# 6_-_Load_Drivers.net
KiCad netlist of a schematic drawn in Altium Designer
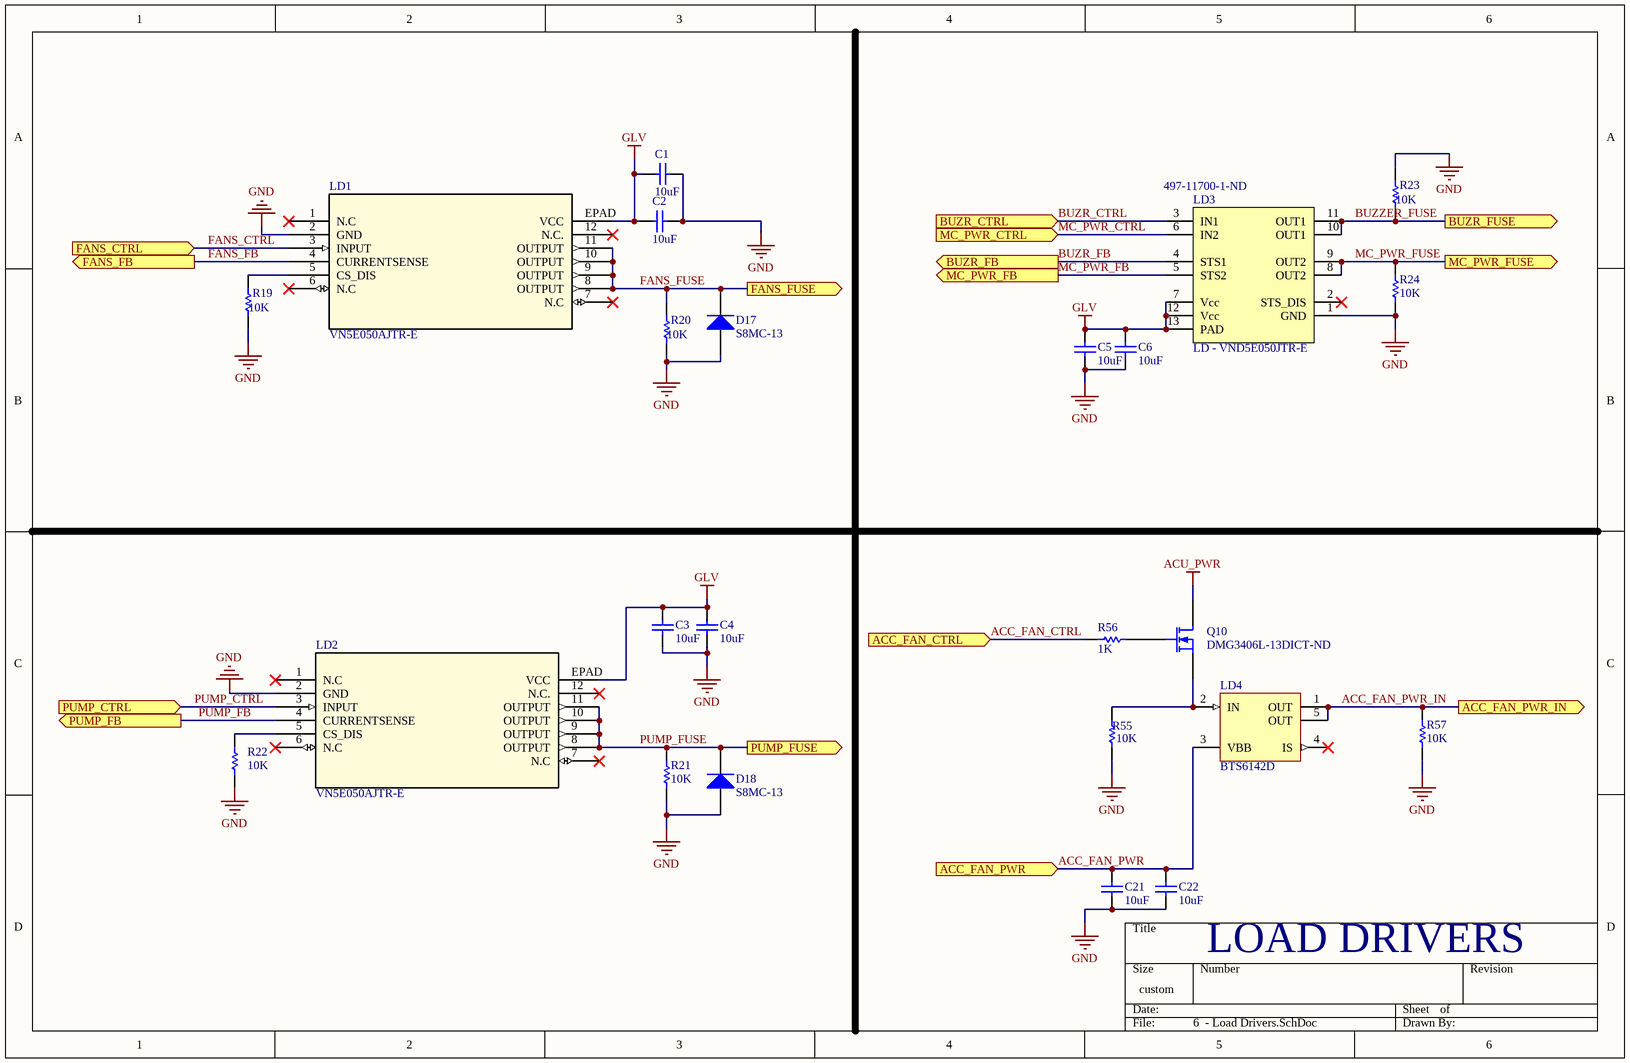
[diagram p0: 6  - Load Drivers.SchDoc]

(export (version "E")
  (design (tool "Eeschema 10.0.6"))
  (components
    (comp (ref "C1")
      (value "10uF")
      (footprint "0603R-generic")
      (description "Capacitor")
      (fields
        (field (name "MANUFACTURER") "Yageo")
        (field (name "MANUFACTURER PART NUMBER") "CC1210ZKY5V8BB106")
      )
      (libsource (lib "Miscellaneous Devices") (part "Cap"))
    )
    (comp (ref "C2")
      (value "10uF")
      (footprint "0603R-generic")
      (description "Capacitor")
      (fields
        (field (name "MANUFACTURER") "Yageo")
        (field (name "MANUFACTURER PART NUMBER") "CC1210ZKY5V8BB106")
      )
      (libsource (lib "Miscellaneous Devices") (part "Cap"))
    )
    (comp (ref "C3")
      (value "10uF")
      (footprint "0603R-generic")
      (description "Capacitor")
      (fields
        (field (name "MANUFACTURER") "Yageo")
        (field (name "MANUFACTURER PART NUMBER") "CC1210ZKY5V8BB106")
      )
      (libsource (lib "Miscellaneous Devices") (part "Cap"))
    )
    (comp (ref "C4")
      (value "10uF")
      (footprint "0603R-generic")
      (description "Capacitor")
      (fields
        (field (name "MANUFACTURER") "Yageo")
        (field (name "MANUFACTURER PART NUMBER") "CC1210ZKY5V8BB106")
      )
      (libsource (lib "Miscellaneous Devices") (part "Cap"))
    )
    (comp (ref "C5")
      (value "10uF")
      (footprint "1608[0603]")
      (description "Capacitor (Semiconductor SIM Model)")
      (fields (field (name "Comment") "Cap Semi") (field (name "PUBLISHER") "Altium Limited"))
      (libsource (lib "Miscellaneous Devices") (part "Cap Semi"))
    )
    (comp (ref "C6")
      (value "10uF")
      (footprint "1608[0603]")
      (description "Capacitor (Semiconductor SIM Model)")
      (fields (field (name "Comment") "Cap Semi") (field (name "PUBLISHER") "Altium Limited"))
      (libsource (lib "Miscellaneous Devices") (part "Cap Semi"))
    )
    (comp (ref "C21")
      (value "10uF")
      (footprint "0603R-generic")
      (description "Capacitor")
      (fields
        (field (name "MANUFACTURER") "Yageo")
        (field (name "MANUFACTURER PART NUMBER") "CC1210ZKY5V8BB106")
      )
      (libsource (lib "Miscellaneous Devices") (part "Cap"))
    )
    (comp (ref "C22")
      (value "10uF")
      (footprint "0603R-generic")
      (description "Capacitor")
      (fields
        (field (name "MANUFACTURER") "Yageo")
        (field (name "MANUFACTURER PART NUMBER") "CC1210ZKY5V8BB106")
      )
      (libsource (lib "Miscellaneous Devices") (part "Cap"))
    )
    (comp (ref "D17")
      (value "S8MC-13")
      (footprint "S8MC-13")
      (description "Default Diode")
      (libsource (lib "Miscellaneous Devices") (part "Diode"))
    )
    (comp (ref "D18")
      (value "S8MC-13")
      (footprint "S8MC-13")
      (description "Default Diode")
      (libsource (lib "Miscellaneous Devices") (part "Diode"))
    )
    (comp (ref "LD1")
      (value "VN5E050AJTR-E")
      (footprint "SO_050AJ-E_STM")
      (libsource (lib "ACB_lib") (part "VN5E050AJTR-E"))
    )
    (comp (ref "LD2")
      (value "VN5E050AJTR-E")
      (footprint "SO_050AJ-E_STM")
      (libsource (lib "ACB_lib") (part "VN5E050AJTR-E"))
    )
    (comp (ref "LD3")
      (value "LD - VND5E050JTR-E")
      (footprint "VND5E050JTR-E")
      (fields (field (name "SUPPLIER PART NUMBER 1") "497-11700-1-ND"))
      (libsource (lib "Power_PCB") (part "LOAD DRIVER - VND5E050JTR-E"))
    )
    (comp (ref "LD4")
      (value "BTS6142D")
      (footprint "INF-PG-TO252-5-11_M")
      (fields (field (name "MANUFACTURER") "Infineon"))
      (libsource (lib "Altium Content Vault") (part "INF-BTS61XXD-PG-TO252-5-11-5"))
    )
    (comp (ref "Q10")
      (value "~")
      (footprint "SOT-23_N")
      (description "N-Channel MOSFET")
      (fields
        (field (name "MANUFACTURER") "Infineon Technologies")
        (field (name "MANUFACTURER PART NUMBER") "IPD075N03L G")
        (field (name "SUPPLIER PART NUMBER 1") "DMG3406L-13DICT-ND")
        (field (name "PUBLISHER") "Altium Limited")
      )
      (libsource (lib "Miscellaneous Devices") (part "MOSFET-N"))
    )
    (comp (ref "R19")
      (value "10K")
      (footprint "RESC0603(1608)_L")
      (description "0603 (1608 Metric) Chip Resistor")
      (libsource (lib "Altium Content Vault") (part "CMP-1591-00001-1"))
    )
    (comp (ref "R20")
      (value "10K")
      (footprint "RESC0603(1608)_L")
      (description "0603 (1608 Metric) Chip Resistor")
      (libsource (lib "Altium Content Vault") (part "CMP-1591-00001-1"))
    )
    (comp (ref "R21")
      (value "10K")
      (footprint "RESC0603(1608)_L")
      (description "0603 (1608 Metric) Chip Resistor")
      (libsource (lib "Altium Content Vault") (part "CMP-1591-00001-1"))
    )
    (comp (ref "R22")
      (value "10K")
      (footprint "RESC0603(1608)_L")
      (description "0603 (1608 Metric) Chip Resistor")
      (libsource (lib "Altium Content Vault") (part "CMP-1591-00001-1"))
    )
    (comp (ref "R23")
      (value "10K")
      (footprint "RESC0603(1608)_L")
      (description "0603 (1608 Metric) Chip Resistor")
      (libsource (lib "Altium Content Vault") (part "CMP-1591-00001-1"))
    )
    (comp (ref "R24")
      (value "10K")
      (footprint "RESC0603(1608)_L")
      (description "0603 (1608 Metric) Chip Resistor")
      (libsource (lib "Altium Content Vault") (part "CMP-1591-00001-1"))
    )
    (comp (ref "R55")
      (value "10K")
      (footprint "RESC0603(1608)_L")
      (description "0603 (1608 Metric) Chip Resistor")
      (libsource (lib "Altium Content Vault") (part "CMP-1591-00001-1"))
    )
    (comp (ref "R56")
      (value "1K")
      (footprint "RESC0603(1608)_L")
      (description "0603 (1608 Metric) Chip Resistor")
      (libsource (lib "Altium Content Vault") (part "RES_3"))
    )
    (comp (ref "R57")
      (value "10K")
      (footprint "RESC0603(1608)_L")
      (description "0603 (1608 Metric) Chip Resistor")
      (libsource (lib "Altium Content Vault") (part "CMP-1591-00001-1"))
    )
  )
  (nets
    (net (code "1") (name "/ACC_FAN_CTRL") (class "Default")
      (node (ref "R56") (pin "1") (pinfunction "1_1") (pintype "passive"))
    )
    (net (code "2") (name "/ACC_FAN_PWR") (class "Default")
      (node (ref "C21") (pin "2") (pinfunction "2_2") (pintype "passive"))
      (node (ref "C22") (pin "2") (pinfunction "2_2") (pintype "passive"))
      (node (ref "LD4") (pin "3") (pinfunction "VBB_3") (pintype "power_in"))
    )
    (net (code "3") (name "/ACC_FAN_PWR_IN") (class "Default")
      (node (ref "LD4") (pin "1") (pinfunction "OUT_1") (pintype "tri_state"))
      (node (ref "LD4") (pin "5") (pinfunction "OUT_5") (pintype "tri_state"))
      (node (ref "R57") (pin "1") (pinfunction "1_1") (pintype "passive"))
    )
    (net (code "4") (name "/BUZR_CTRL") (class "Default")
      (node (ref "LD3") (pin "3") (pinfunction "IN1_3") (pintype "passive"))
    )
    (net (code "5") (name "/BUZR_FB") (class "Default")
      (node (ref "LD3") (pin "4") (pinfunction "STS1_4") (pintype "passive"))
    )
    (net (code "6") (name "/BUZZER_FUSE") (class "Default")
      (node (ref "LD3") (pin "10") (pinfunction "OUT1_10") (pintype "passive"))
      (node (ref "LD3") (pin "11") (pinfunction "OUT1_11") (pintype "passive"))
      (node (ref "R23") (pin "1") (pinfunction "1_1") (pintype "passive"))
    )
    (net (code "7") (name "/FANS_CTRL") (class "Default")
      (node (ref "LD1") (pin "3") (pinfunction "INPUT_3") (pintype "input"))
    )
    (net (code "8") (name "/FANS_FB") (class "Default")
      (node (ref "LD1") (pin "4") (pinfunction "CURRENTSENSE_4") (pintype "passive"))
    )
    (net (code "9") (name "/FANS_FUSE") (class "Default")
      (node (ref "D17") (pin "2") (pinfunction "K_2") (pintype "passive"))
      (node (ref "LD1") (pin "10") (pinfunction "OUTPUT_10") (pintype "output"))
      (node (ref "LD1") (pin "11") (pinfunction "OUTPUT_11") (pintype "output"))
      (node (ref "LD1") (pin "8") (pinfunction "OUTPUT_8") (pintype "output"))
      (node (ref "LD1") (pin "9") (pinfunction "OUTPUT_9") (pintype "output"))
      (node (ref "R20") (pin "2") (pinfunction "2_2") (pintype "passive"))
    )
    (net (code "10") (name "/MC_PWR_CTRL") (class "Default")
      (node (ref "LD3") (pin "6") (pinfunction "IN2_6") (pintype "passive"))
    )
    (net (code "11") (name "/MC_PWR_FB") (class "Default")
      (node (ref "LD3") (pin "5") (pinfunction "STS2_5") (pintype "passive"))
    )
    (net (code "12") (name "/MC_PWR_FUSE") (class "Default")
      (node (ref "LD3") (pin "8") (pinfunction "OUT2_8") (pintype "passive"))
      (node (ref "LD3") (pin "9") (pinfunction "OUT2_9") (pintype "passive"))
      (node (ref "R24") (pin "1") (pinfunction "1_1") (pintype "passive"))
    )
    (net (code "13") (name "/PUMP_CTRL") (class "Default")
      (node (ref "LD2") (pin "3") (pinfunction "INPUT_3") (pintype "input"))
    )
    (net (code "14") (name "/PUMP_FB") (class "Default")
      (node (ref "LD2") (pin "4") (pinfunction "CURRENTSENSE_4") (pintype "passive"))
    )
    (net (code "15") (name "/PUMP_FUSE") (class "Default")
      (node (ref "D18") (pin "2") (pinfunction "K_2") (pintype "passive"))
      (node (ref "LD2") (pin "10") (pinfunction "OUTPUT_10") (pintype "output"))
      (node (ref "LD2") (pin "11") (pinfunction "OUTPUT_11") (pintype "output"))
      (node (ref "LD2") (pin "8") (pinfunction "OUTPUT_8") (pintype "output"))
      (node (ref "LD2") (pin "9") (pinfunction "OUTPUT_9") (pintype "output"))
      (node (ref "R21") (pin "2") (pinfunction "2_2") (pintype "passive"))
    )
    (net (code "16") (name "ACU_PWR") (class "Default")
      (node (ref "Q10") (pin "3") (pinfunction "D_3") (pintype "passive"))
    )
    (net (code "17") (name "GLV") (class "Default")
      (node (ref "C1") (pin "2") (pinfunction "2_2") (pintype "passive"))
      (node (ref "C2") (pin "2") (pinfunction "2_2") (pintype "passive"))
      (node (ref "C3") (pin "2") (pinfunction "2_2") (pintype "passive"))
      (node (ref "C4") (pin "2") (pinfunction "2_2") (pintype "passive"))
      (node (ref "C5") (pin "2") (pinfunction "2_2") (pintype "passive"))
      (node (ref "C6") (pin "2") (pinfunction "2_2") (pintype "passive"))
      (node (ref "LD1") (pin "EPAD") (pinfunction "VCC_EPAD") (pintype "power_in"))
      (node (ref "LD2") (pin "EPAD") (pinfunction "VCC_EPAD") (pintype "power_in"))
      (node (ref "LD3") (pin "12") (pinfunction "Vcc_12") (pintype "passive"))
      (node (ref "LD3") (pin "13") (pinfunction "PAD_13") (pintype "passive"))
      (node (ref "LD3") (pin "7") (pinfunction "Vcc_7") (pintype "passive"))
    )
    (net (code "18") (name "GND") (class "Default")
      (node (ref "C1") (pin "1") (pinfunction "1_1") (pintype "passive"))
      (node (ref "C2") (pin "1") (pinfunction "1_1") (pintype "passive"))
      (node (ref "C21") (pin "1") (pinfunction "1_1") (pintype "passive"))
      (node (ref "C22") (pin "1") (pinfunction "1_1") (pintype "passive"))
      (node (ref "C3") (pin "1") (pinfunction "1_1") (pintype "passive"))
      (node (ref "C4") (pin "1") (pinfunction "1_1") (pintype "passive"))
      (node (ref "C5") (pin "1") (pinfunction "1_1") (pintype "passive"))
      (node (ref "C6") (pin "1") (pinfunction "1_1") (pintype "passive"))
      (node (ref "D17") (pin "1") (pinfunction "A_1") (pintype "passive"))
      (node (ref "D18") (pin "1") (pinfunction "A_1") (pintype "passive"))
      (node (ref "LD1") (pin "2") (pinfunction "GND_2") (pintype "power_in"))
      (node (ref "LD2") (pin "2") (pinfunction "GND_2") (pintype "power_in"))
      (node (ref "LD3") (pin "1") (pinfunction "GND_1") (pintype "passive"))
      (node (ref "R19") (pin "1") (pinfunction "1_1") (pintype "passive"))
      (node (ref "R20") (pin "1") (pinfunction "1_1") (pintype "passive"))
      (node (ref "R21") (pin "1") (pinfunction "1_1") (pintype "passive"))
      (node (ref "R22") (pin "1") (pinfunction "1_1") (pintype "passive"))
      (node (ref "R23") (pin "2") (pinfunction "2_2") (pintype "passive"))
      (node (ref "R24") (pin "2") (pinfunction "2_2") (pintype "passive"))
      (node (ref "R55") (pin "2") (pinfunction "2_2") (pintype "passive"))
      (node (ref "R57") (pin "2") (pinfunction "2_2") (pintype "passive"))
    )
    (net (code "19") (name "Net-(LD1-CS_DIS)") (class "Default")
      (node (ref "LD1") (pin "5") (pinfunction "CS_DIS_5") (pintype "passive"))
      (node (ref "R19") (pin "2") (pinfunction "2_2") (pintype "passive"))
    )
    (net (code "20") (name "Net-(LD2-CS_DIS)") (class "Default")
      (node (ref "LD2") (pin "5") (pinfunction "CS_DIS_5") (pintype "passive"))
      (node (ref "R22") (pin "2") (pinfunction "2_2") (pintype "passive"))
    )
    (net (code "21") (name "Net-(LD4-IN)") (class "Default")
      (node (ref "LD4") (pin "2") (pinfunction "IN_2") (pintype "input"))
      (node (ref "Q10") (pin "2") (pinfunction "S_2") (pintype "passive"))
      (node (ref "R55") (pin "1") (pinfunction "1_1") (pintype "passive"))
    )
    (net (code "22") (name "Net-(Q10-G)") (class "Default")
      (node (ref "Q10") (pin "1") (pinfunction "G_1") (pintype "passive"))
      (node (ref "R56") (pin "2") (pinfunction "2_2") (pintype "passive"))
    )
    (net (code "23") (name "unconnected-(LD1-N.C-Pad1)") (class "Default")
      (node (ref "LD1") (pin "1") (pinfunction "N.C_1") (pintype "passive+no_connect"))
    )
    (net (code "24") (name "unconnected-(LD1-N.C-Pad6)") (class "Default")
      (node (ref "LD1") (pin "6") (pinfunction "N.C_6") (pintype "bidirectional+no_connect"))
    )
    (net (code "25") (name "unconnected-(LD1-N.C-Pad7)") (class "Default")
      (node (ref "LD1") (pin "7") (pinfunction "N.C_7") (pintype "bidirectional+no_connect"))
    )
    (net (code "26") (name "unconnected-(LD1-N.C.-Pad12)") (class "Default")
      (node (ref "LD1") (pin "12") (pinfunction "N.C._12") (pintype "passive+no_connect"))
    )
    (net (code "27") (name "unconnected-(LD2-N.C-Pad1)") (class "Default")
      (node (ref "LD2") (pin "1") (pinfunction "N.C_1") (pintype "passive+no_connect"))
    )
    (net (code "28") (name "unconnected-(LD2-N.C-Pad6)") (class "Default")
      (node (ref "LD2") (pin "6") (pinfunction "N.C_6") (pintype "bidirectional+no_connect"))
    )
    (net (code "29") (name "unconnected-(LD2-N.C-Pad7)") (class "Default")
      (node (ref "LD2") (pin "7") (pinfunction "N.C_7") (pintype "bidirectional+no_connect"))
    )
    (net (code "30") (name "unconnected-(LD2-N.C.-Pad12)") (class "Default")
      (node (ref "LD2") (pin "12") (pinfunction "N.C._12") (pintype "passive+no_connect"))
    )
    (net (code "31") (name "unconnected-(LD3-STS_DIS-Pad2)") (class "Default")
      (node (ref "LD3") (pin "2") (pinfunction "STS_DIS_2") (pintype "passive+no_connect"))
    )
    (net (code "32") (name "unconnected-(LD4-IS-Pad4)") (class "Default")
      (node (ref "LD4") (pin "4") (pinfunction "IS_4") (pintype "output+no_connect"))
    )
  )
)
